# 3_3V_BuckDesign.net
KiCad netlist of a schematic drawn in Altium Designer
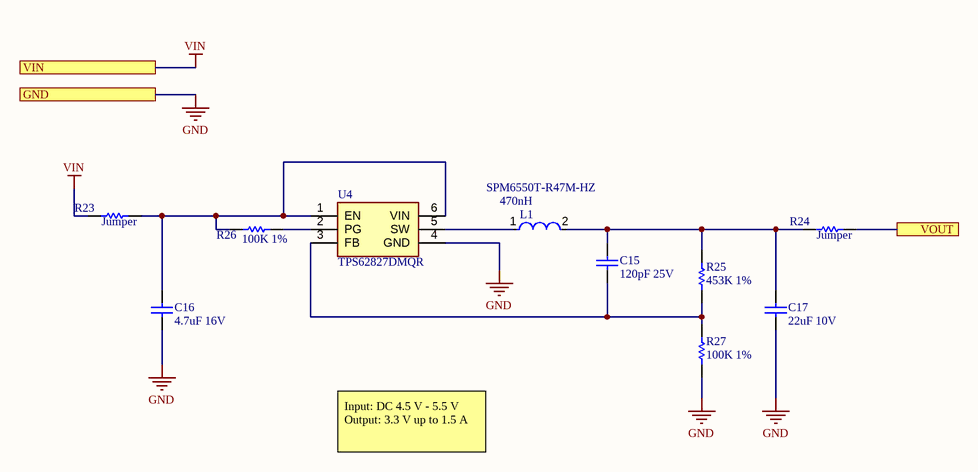
[diagram p0: 3.3V_BuckDesign.SchDoc]

(export (version "E")
  (design (tool "Eeschema 10.0.6"))
  (components
    (comp (ref "C15")
      (value "120pF 25V")
      (footprint "CAPC0603(1608)100_N")
      (description "CAP 120pF 25V ±1% 0603 (1608 Metric) Thickness 1mm SMD")
      (fields (field (name "TOLERANCE") "Â±1%"))
      (libsource (lib "Altium Content Vault") (part "CAP"))
    )
    (comp (ref "C16")
      (value "4.7uF 16V")
      (footprint "CAPC0805(2012)145_N")
      (description "CAP 4.7uF 16V -20% to +80% 0805 (2012 Metric) Thickness 1.45mm SMD")
      (fields (field (name "TOLERANCE") "-20% to +80%"))
      (libsource (lib "Altium Content Vault") (part "CAP"))
    )
    (comp (ref "C17")
      (value "22uF 10V")
      (footprint "CAPC0805(2012)100_L")
      (description "CAP 22uF 10V ±20% 0805 (2012 Metric) Thickness 1mm SMD")
      (fields (field (name "TOLERANCE") "Â±20%"))
      (libsource (lib "Altium Content Vault") (part "CAP"))
    )
    (comp (ref "L1")
      (value "SPM6550T-R47M-HZ")
      (footprint "FP-SPM6550-MFG")
      (description "FIX IND 470NH 26.1A 2.97MOHM SMD")
      (fields
        (field (name "INDUCTANCE") "470nH")
        (field (name "MANUFACTURER") "TDK")
        (field (name "TOLERANCE") "20%")
      )
      (libsource (lib "Inductor") (part "CMP-08253-000017-1"))
    )
    (comp (ref "R23")
      (value "Jumper")
      (footprint "RESC0603(1608)_N")
      (description "Jumper 0603 (1608 Metric)")
      (fields (field (name "POWER") "None"))
      (libsource (lib "Altium Content Vault") (part "RES"))
    )
    (comp (ref "R24")
      (value "Jumper")
      (footprint "RESC0603(1608)_N")
      (description "Jumper 0603 (1608 Metric)")
      (fields (field (name "POWER") "None"))
      (libsource (lib "Altium Content Vault") (part "RES"))
    )
    (comp (ref "R25")
      (value "453K 1%")
      (footprint "RESC0402(1005)_L")
      (description "453K 0.063W 1% 0402 (1005 Metric)  SMD")
      (fields (field (name "TOLERANCE") "1 %") (field (name "POWER") "0.063 W"))
      (libsource (lib "Altium Content Vault") (part "RES"))
    )
    (comp (ref "R26")
      (value "100K 1%")
      (footprint "RESC0603(1608)_N")
      (description "100K 0.1W 1% 0603 (1608 Metric)  SMD")
      (fields (field (name "POWER") "0.1 W") (field (name "TOLERANCE") "1 %"))
      (libsource (lib "Altium Content Vault") (part "RES"))
    )
    (comp (ref "R27")
      (value "100K 1%")
      (footprint "RESC0603(1608)_N")
      (description "100K 0.1W 1% 0603 (1608 Metric)  SMD")
      (fields (field (name "POWER") "0.1 W") (field (name "TOLERANCE") "1 %"))
      (libsource (lib "Altium Content Vault") (part "RES"))
    )
    (comp (ref "U4")
      (value "TPS62827DMQR")
      (footprint "SamacSys:TPS6282518DMQR")
      (description "2.4V-5.5V input, 4A step-down converter with 1% Accuracy in 1.5mm x 1.5mm QFN 6-VSON-HR -40 to 125")
      (fields (field (name "MOUSER PART NUMBER") "595-TPS62827DMQR"))
      (libsource (lib "*") (part "TPS62827DMQR"))
    )
  )
  (nets
    (net (code "1") (name "/VOUT") (class "Default")
      (node (ref "R24") (pin "2") (pinfunction "2_2") (pintype "passive"))
    )
    (net (code "2") (name "GND") (class "Default")
      (node (ref "C16") (pin "1") (pinfunction "1_1") (pintype "passive"))
      (node (ref "C17") (pin "1") (pinfunction "1_1") (pintype "passive"))
      (node (ref "R27") (pin "1") (pinfunction "1_1") (pintype "passive"))
      (node (ref "U4") (pin "4") (pinfunction "GND_4") (pintype "passive"))
    )
    (net (code "3") (name "Net-(C15-Pad2)") (class "Default")
      (node (ref "C15") (pin "2") (pinfunction "2_2") (pintype "passive"))
      (node (ref "C17") (pin "2") (pinfunction "2_2") (pintype "passive"))
      (node (ref "L1") (pin "2") (pinfunction "2_2") (pintype "passive"))
      (node (ref "R24") (pin "1") (pinfunction "1_1") (pintype "passive"))
      (node (ref "R25") (pin "2") (pinfunction "2_2") (pintype "passive"))
    )
    (net (code "4") (name "Net-(U4-EN)") (class "Default")
      (node (ref "C16") (pin "2") (pinfunction "2_2") (pintype "passive"))
      (node (ref "R23") (pin "2") (pinfunction "2_2") (pintype "passive"))
      (node (ref "R26") (pin "1") (pinfunction "1_1") (pintype "passive"))
      (node (ref "U4") (pin "1") (pinfunction "EN_1") (pintype "passive"))
      (node (ref "U4") (pin "6") (pinfunction "VIN_6") (pintype "passive"))
    )
    (net (code "5") (name "Net-(U4-FB)") (class "Default")
      (node (ref "C15") (pin "1") (pinfunction "1_1") (pintype "passive"))
      (node (ref "R25") (pin "1") (pinfunction "1_1") (pintype "passive"))
      (node (ref "R27") (pin "2") (pinfunction "2_2") (pintype "passive"))
      (node (ref "U4") (pin "3") (pinfunction "FB_3") (pintype "passive"))
    )
    (net (code "6") (name "Net-(U4-PG)") (class "Default")
      (node (ref "R26") (pin "2") (pinfunction "2_2") (pintype "passive"))
      (node (ref "U4") (pin "2") (pinfunction "PG_2") (pintype "passive"))
    )
    (net (code "7") (name "Net-(U4-SW)") (class "Default")
      (node (ref "L1") (pin "1") (pinfunction "1_1") (pintype "passive"))
      (node (ref "U4") (pin "5") (pinfunction "SW_5") (pintype "passive"))
    )
    (net (code "8") (name "VIN") (class "Default")
      (node (ref "R23") (pin "1") (pinfunction "1_1") (pintype "passive"))
    )
  )
)
